# Fastino-DIOT.net
KiCad netlist of a schematic drawn in Altium Designer
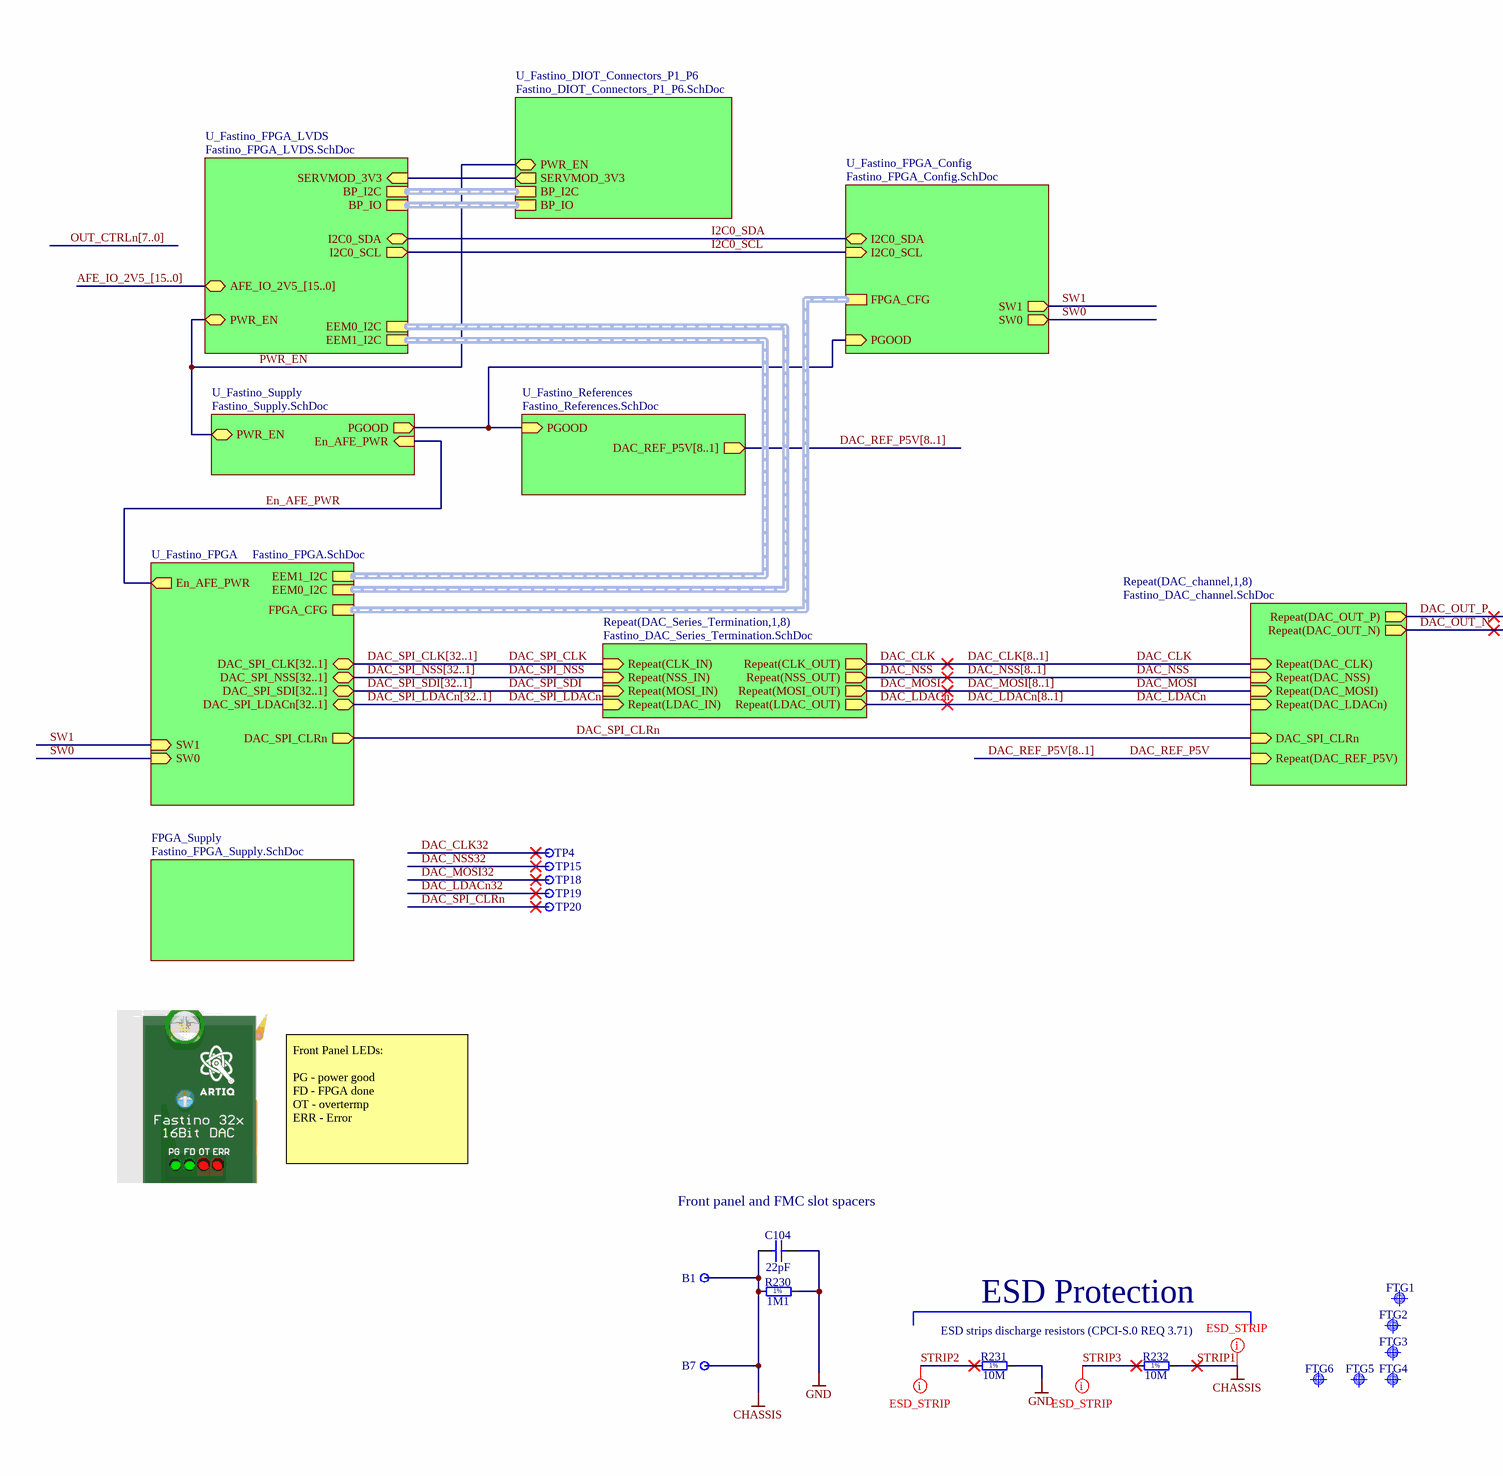
[diagram p0: Fastino-DIOT.schdoc, left]
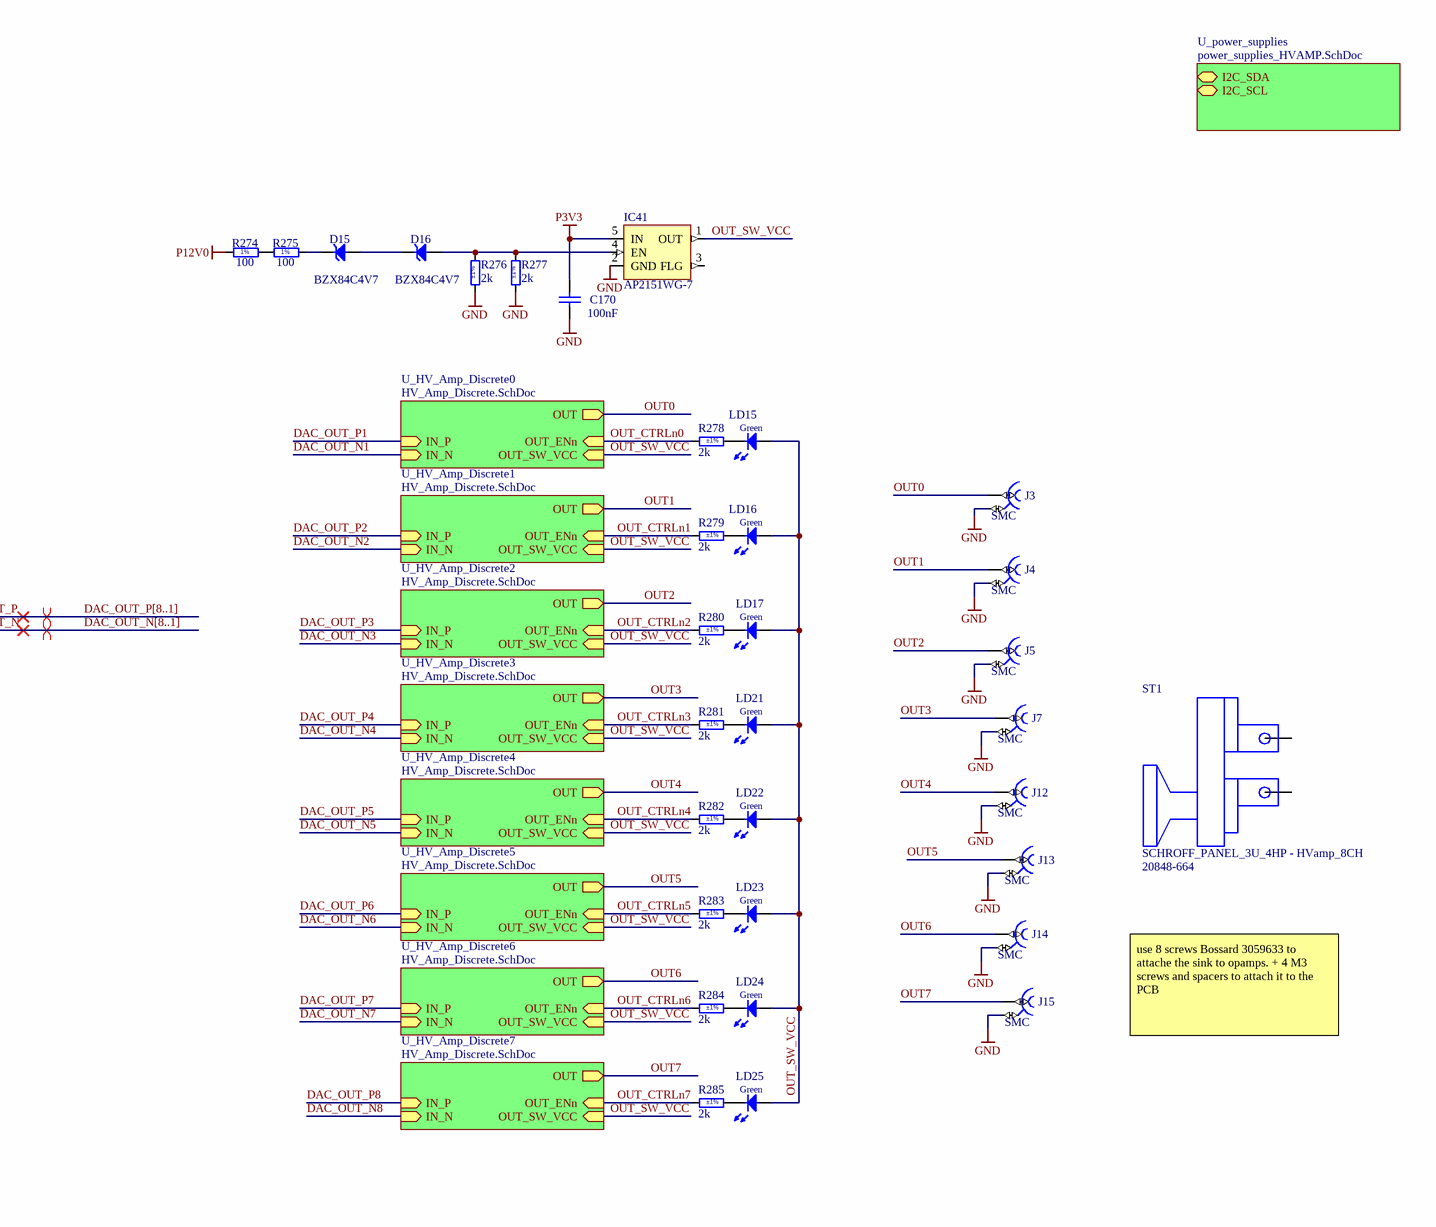
[diagram p1: Fastino-DIOT.schdoc, right]

(export (version "E")
  (design (tool "Eeschema 10.0.6"))
  (components
    (comp (ref "B1")
      (value "Plated Hole")
      (footprint "MTG270_500")
      (description "Single Terminal Socket")
      (fields (field (name "PART NUMBER") "PLATED_HOLE2.7_PAD5.0") (field (name "AUTHOR") "CERN DEM JMW"))
      (libsource (lib "Eletro-mechanical") (part "Single Terminal Socket"))
    )
    (comp (ref "B7")
      (value "Plated Hole")
      (footprint "MTG270_500")
      (description "Single Terminal Socket")
      (fields (field (name "PART NUMBER") "PLATED_HOLE2.7_PAD5.0") (field (name "AUTHOR") "CERN DEM JMW"))
      (libsource (lib "Eletro-mechanical") (part "Single Terminal Socket"))
    )
    (comp (ref "C104")
      (value "22pF")
      (footprint "CAPC1005X55N")
      (description "Non-polarised capacitor")
      (fields
        (field (name "PART NUMBER") "CC0402_22PF_50V_5%_C0G")
        (field (name "VOLTAGE") "50V")
        (field (name "AUTHOR") "CERN DEM JLC")
      )
      (libsource (lib "Capacitors") (part "Capacitor - non polarized"))
    )
    (comp (ref "C170")
      (value "100nF")
      (footprint "CAPC1005X55N")
      (description "Non-polarised capacitor")
      (fields
        (field (name "PART NUMBER") "CC0402_100NF_16V_10%_X5R")
        (field (name "VOLTAGE") "16V")
        (field (name "AUTHOR") "CERN DEM JLC")
      )
      (libsource (lib "Capacitors") (part "Capacitor - non polarized"))
    )
    (comp (ref "D15")
      (value "BZX84C4V7")
      (footprint "SOT95P240X130-3N")
      (description "Diode Zener Anode Pin 1 Cathode Pin 3 (Pas de pin 2)")
      (fields
        (field (name "VOLTAGE") "4V7")
        (field (name "POWER") "350mW")
        (field (name "AUTHOR") "CERN DEM JLC")
      )
      (libsource (lib "ICs And Semiconductors") (part "Diode Zener A1C3"))
    )
    (comp (ref "D16")
      (value "BZX84C4V7")
      (footprint "SOT95P240X130-3N")
      (description "Diode Zener Anode Pin 1 Cathode Pin 3 (Pas de pin 2)")
      (fields
        (field (name "VOLTAGE") "4V7")
        (field (name "POWER") "350mW")
        (field (name "AUTHOR") "CERN DEM JLC")
      )
      (libsource (lib "ICs And Semiconductors") (part "Diode Zener A1C3"))
    )
    (comp (ref "FTG1")
      (value "Use only in PCB")
      (footprint "FIDUCIAL_TOP_C100-200")
      (description "Fiducial Target")
      (fields (field (name "PART NUMBER") "FIDUCIAL_TARGET_C100-200") (field (name "AUTHOR") "CERN DEM JLC"))
      (libsource (lib "Eletro-mechanical") (part "Fiducial Target"))
    )
    (comp (ref "FTG2")
      (value "Use only in PCB")
      (footprint "FIDUCIAL_TOP_S100-200")
      (description "Fiducial Target")
      (fields (field (name "PART NUMBER") "FIDUCIAL_TARGET_S100-200") (field (name "AUTHOR") "CERN DEM JLC"))
      (libsource (lib "Eletro-mechanical") (part "Fiducial Target"))
    )
    (comp (ref "FTG3")
      (value "Use only in PCB")
      (footprint "FIDUCIAL_TOP_S100-200")
      (description "Fiducial Target")
      (fields (field (name "PART NUMBER") "FIDUCIAL_TARGET_S100-200") (field (name "AUTHOR") "CERN DEM JLC"))
      (libsource (lib "Eletro-mechanical") (part "Fiducial Target"))
    )
    (comp (ref "FTG4")
      (value "Use only in PCB")
      (footprint "FIDUCIAL_TOP_S100-200")
      (description "Fiducial Target")
      (fields (field (name "PART NUMBER") "FIDUCIAL_TARGET_S100-200") (field (name "AUTHOR") "CERN DEM JLC"))
      (libsource (lib "Eletro-mechanical") (part "Fiducial Target"))
    )
    (comp (ref "FTG5")
      (value "Use only in PCB")
      (footprint "FIDUCIAL_TOP_S100-200")
      (description "Fiducial Target")
      (fields (field (name "PART NUMBER") "FIDUCIAL_TARGET_S100-200") (field (name "AUTHOR") "CERN DEM JLC"))
      (libsource (lib "Eletro-mechanical") (part "Fiducial Target"))
    )
    (comp (ref "FTG6")
      (value "Use only in PCB")
      (footprint "FIDUCIAL_TOP_S100-200")
      (description "Fiducial Target")
      (fields (field (name "PART NUMBER") "FIDUCIAL_TARGET_S100-200") (field (name "AUTHOR") "CERN DEM JLC"))
      (libsource (lib "Eletro-mechanical") (part "Fiducial Target"))
    )
    (comp (ref "IC41")
      (value "AP2151WG-7")
      (footprint "SOT23-5")
      (description "0.5A SINGLE CHANNEL CURRENT- LIMITED POWER Switch")
      (libsource (lib "ICs_Analog_Interfaces") (part "IFC_AP2151"))
    )
    (comp (ref "J3")
      (value "SMC")
      (footprint "JOHNSON_131-6701-341")
      (fields
        (field (name "PART NUMBER") "JOHNSON_131-6701-341")
        (field (name "MANUFACTURER") "JOHNSON")
        (field (name "MANUFACTURER PART NUMBER") "131-6701-341")
        (field (name "AUTHOR") "CERN DEM JLC")
      )
      (libsource (lib "Connectors") (part "Coax_1Female_1Shield"))
    )
    (comp (ref "J4")
      (value "SMC")
      (footprint "JOHNSON_131-6701-341")
      (fields
        (field (name "PART NUMBER") "JOHNSON_131-6701-341")
        (field (name "MANUFACTURER") "JOHNSON")
        (field (name "MANUFACTURER PART NUMBER") "131-6701-341")
        (field (name "AUTHOR") "CERN DEM JLC")
      )
      (libsource (lib "Connectors") (part "Coax_1Female_1Shield"))
    )
    (comp (ref "J5")
      (value "SMC")
      (footprint "JOHNSON_131-6701-341")
      (fields
        (field (name "PART NUMBER") "JOHNSON_131-6701-341")
        (field (name "MANUFACTURER") "JOHNSON")
        (field (name "MANUFACTURER PART NUMBER") "131-6701-341")
        (field (name "AUTHOR") "CERN DEM JLC")
      )
      (libsource (lib "Connectors") (part "Coax_1Female_1Shield"))
    )
    (comp (ref "J7")
      (value "SMC")
      (footprint "JOHNSON_131-6701-341")
      (fields
        (field (name "PART NUMBER") "JOHNSON_131-6701-341")
        (field (name "MANUFACTURER") "JOHNSON")
        (field (name "MANUFACTURER PART NUMBER") "131-6701-341")
        (field (name "AUTHOR") "CERN DEM JLC")
      )
      (libsource (lib "Connectors") (part "Coax_1Female_1Shield"))
    )
    (comp (ref "J12")
      (value "SMC")
      (footprint "JOHNSON_131-6701-341")
      (fields
        (field (name "PART NUMBER") "JOHNSON_131-6701-341")
        (field (name "MANUFACTURER") "JOHNSON")
        (field (name "MANUFACTURER PART NUMBER") "131-6701-341")
        (field (name "AUTHOR") "CERN DEM JLC")
      )
      (libsource (lib "Connectors") (part "Coax_1Female_1Shield"))
    )
    (comp (ref "J13")
      (value "SMC")
      (footprint "JOHNSON_131-6701-341")
      (fields
        (field (name "PART NUMBER") "JOHNSON_131-6701-341")
        (field (name "MANUFACTURER") "JOHNSON")
        (field (name "MANUFACTURER PART NUMBER") "131-6701-341")
        (field (name "AUTHOR") "CERN DEM JLC")
      )
      (libsource (lib "Connectors") (part "Coax_1Female_1Shield"))
    )
    (comp (ref "J14")
      (value "SMC")
      (footprint "JOHNSON_131-6701-341")
      (fields
        (field (name "PART NUMBER") "JOHNSON_131-6701-341")
        (field (name "MANUFACTURER") "JOHNSON")
        (field (name "MANUFACTURER PART NUMBER") "131-6701-341")
        (field (name "AUTHOR") "CERN DEM JLC")
      )
      (libsource (lib "Connectors") (part "Coax_1Female_1Shield"))
    )
    (comp (ref "J15")
      (value "SMC")
      (footprint "JOHNSON_131-6701-341")
      (fields
        (field (name "PART NUMBER") "JOHNSON_131-6701-341")
        (field (name "MANUFACTURER") "JOHNSON")
        (field (name "MANUFACTURER PART NUMBER") "131-6701-341")
        (field (name "AUTHOR") "CERN DEM JLC")
      )
      (libsource (lib "Connectors") (part "Coax_1Female_1Shield"))
    )
    (comp (ref "LD15")
      (value "Green")
      (footprint "LED_AVAGO_HSME-C120")
      (description "LED Green 1C 2A")
      (fields
        (field (name "PART NUMBER") "LED_AVAGO_HSME-C120")
        (field (name "MANUFACTURER") "AVAGO TECHNOLOGIES")
        (field (name "AUTHOR") "CERN DEM JMW")
      )
      (libsource (lib "ICs And Semiconductors") (part "LED Green 1C 2A"))
    )
    (comp (ref "LD16")
      (value "Green")
      (footprint "LED_AVAGO_HSME-C120")
      (description "LED Green 1C 2A")
      (fields
        (field (name "PART NUMBER") "LED_AVAGO_HSME-C120")
        (field (name "MANUFACTURER") "AVAGO TECHNOLOGIES")
        (field (name "AUTHOR") "CERN DEM JMW")
      )
      (libsource (lib "ICs And Semiconductors") (part "LED Green 1C 2A"))
    )
    (comp (ref "LD17")
      (value "Green")
      (footprint "LED_AVAGO_HSME-C120")
      (description "LED Green 1C 2A")
      (fields
        (field (name "PART NUMBER") "LED_AVAGO_HSME-C120")
        (field (name "MANUFACTURER") "AVAGO TECHNOLOGIES")
        (field (name "AUTHOR") "CERN DEM JMW")
      )
      (libsource (lib "ICs And Semiconductors") (part "LED Green 1C 2A"))
    )
    (comp (ref "LD21")
      (value "Green")
      (footprint "LED_AVAGO_HSME-C120")
      (description "LED Green 1C 2A")
      (fields
        (field (name "PART NUMBER") "LED_AVAGO_HSME-C120")
        (field (name "MANUFACTURER") "AVAGO TECHNOLOGIES")
        (field (name "AUTHOR") "CERN DEM JMW")
      )
      (libsource (lib "ICs And Semiconductors") (part "LED Green 1C 2A"))
    )
    (comp (ref "LD22")
      (value "Green")
      (footprint "LED_AVAGO_HSME-C120")
      (description "LED Green 1C 2A")
      (fields
        (field (name "PART NUMBER") "LED_AVAGO_HSME-C120")
        (field (name "MANUFACTURER") "AVAGO TECHNOLOGIES")
        (field (name "AUTHOR") "CERN DEM JMW")
      )
      (libsource (lib "ICs And Semiconductors") (part "LED Green 1C 2A"))
    )
    (comp (ref "LD23")
      (value "Green")
      (footprint "LED_AVAGO_HSME-C120")
      (description "LED Green 1C 2A")
      (fields
        (field (name "PART NUMBER") "LED_AVAGO_HSME-C120")
        (field (name "MANUFACTURER") "AVAGO TECHNOLOGIES")
        (field (name "AUTHOR") "CERN DEM JMW")
      )
      (libsource (lib "ICs And Semiconductors") (part "LED Green 1C 2A"))
    )
    (comp (ref "LD24")
      (value "Green")
      (footprint "LED_AVAGO_HSME-C120")
      (description "LED Green 1C 2A")
      (fields
        (field (name "PART NUMBER") "LED_AVAGO_HSME-C120")
        (field (name "MANUFACTURER") "AVAGO TECHNOLOGIES")
        (field (name "AUTHOR") "CERN DEM JMW")
      )
      (libsource (lib "ICs And Semiconductors") (part "LED Green 1C 2A"))
    )
    (comp (ref "LD25")
      (value "Green")
      (footprint "LED_AVAGO_HSME-C120")
      (description "LED Green 1C 2A")
      (fields
        (field (name "PART NUMBER") "LED_AVAGO_HSME-C120")
        (field (name "MANUFACTURER") "AVAGO TECHNOLOGIES")
        (field (name "AUTHOR") "CERN DEM JMW")
      )
      (libsource (lib "ICs And Semiconductors") (part "LED Green 1C 2A"))
    )
    (comp (ref "R230")
      (value "1M1")
      (footprint "RESC2012X60N")
      (description "Resistor - 1%")
      (fields
        (field (name "PART NUMBER") "R0805_1M1_1%_0.125W_100PPM")
        (field (name "POWER") "0.125W")
        (field (name "AUTHOR") "CERN DEM JLC")
      )
      (libsource (lib "") (part "Resistor - 1%_1"))
    )
    (comp (ref "R231")
      (value "10M")
      (footprint "RESC2113X55N")
      (description "Resistor - 1%")
      (fields
        (field (name "PART NUMBER") "R0805_10M_1%_0.125W_100PPM_VISHAY_CRCW e3")
        (field (name "POWER") "0.125W")
        (field (name "AUTHOR") "CERN DEM BC")
      )
      (libsource (lib "") (part "Resistor - 1%_1"))
    )
    (comp (ref "R232")
      (value "10M")
      (footprint "RESC2113X55N")
      (description "Resistor - 1%")
      (fields
        (field (name "PART NUMBER") "R0805_10M_1%_0.125W_100PPM_VISHAY_CRCW e3")
        (field (name "POWER") "0.125W")
        (field (name "AUTHOR") "CERN DEM BC")
      )
      (libsource (lib "") (part "Resistor - 1%_1"))
    )
    (comp (ref "R274")
      (value "100")
      (footprint "RESC1005X40N")
      (description "Resistor - 1%")
      (fields
        (field (name "PART NUMBER") "R0402_100R_1%_0.0625W_100PPM")
        (field (name "POWER") "0.0625W")
        (field (name "AUTHOR") "CERN DEM JLC")
      )
      (libsource (lib "Resistors") (part "Resistor - 1%"))
    )
    (comp (ref "R275")
      (value "100")
      (footprint "RESC1005X40N")
      (description "Resistor - 1%")
      (fields
        (field (name "PART NUMBER") "R0402_100R_1%_0.0625W_100PPM")
        (field (name "POWER") "0.0625W")
        (field (name "AUTHOR") "CERN DEM JLC")
      )
      (libsource (lib "Resistors") (part "Resistor - 1%"))
    )
    (comp (ref "R276")
      (value "2k")
      (footprint "RESC1005X40N")
      (description "Resistor - 1%")
      (fields
        (field (name "PART NUMBER") "R0402_2K_1%_0.0625W_100PPM")
        (field (name "POWER") "0.0625W")
        (field (name "TOLERANCE") "±1%")
        (field (name "AUTHOR") "CERN DEM JLC")
      )
      (libsource (lib "Resistors") (part "Resistor - 1%"))
    )
    (comp (ref "R277")
      (value "2k")
      (footprint "RESC1005X40N")
      (description "Resistor - 1%")
      (fields
        (field (name "PART NUMBER") "R0402_2K_1%_0.0625W_100PPM")
        (field (name "POWER") "0.0625W")
        (field (name "TOLERANCE") "±1%")
        (field (name "AUTHOR") "CERN DEM JLC")
      )
      (libsource (lib "Resistors") (part "Resistor - 1%"))
    )
    (comp (ref "R278")
      (value "2k")
      (footprint "RESC1005X40N")
      (description "Resistor - 1%")
      (fields
        (field (name "PART NUMBER") "R0402_2K_1%_0.0625W_100PPM")
        (field (name "POWER") "0.0625W")
        (field (name "TOLERANCE") "±1%")
        (field (name "AUTHOR") "CERN DEM JLC")
      )
      (libsource (lib "Resistors") (part "Resistor - 1%"))
    )
    (comp (ref "R279")
      (value "2k")
      (footprint "RESC1005X40N")
      (description "Resistor - 1%")
      (fields
        (field (name "PART NUMBER") "R0402_2K_1%_0.0625W_100PPM")
        (field (name "POWER") "0.0625W")
        (field (name "TOLERANCE") "±1%")
        (field (name "AUTHOR") "CERN DEM JLC")
      )
      (libsource (lib "Resistors") (part "Resistor - 1%"))
    )
    (comp (ref "R280")
      (value "2k")
      (footprint "RESC1005X40N")
      (description "Resistor - 1%")
      (fields
        (field (name "PART NUMBER") "R0402_2K_1%_0.0625W_100PPM")
        (field (name "POWER") "0.0625W")
        (field (name "TOLERANCE") "±1%")
        (field (name "AUTHOR") "CERN DEM JLC")
      )
      (libsource (lib "Resistors") (part "Resistor - 1%"))
    )
    (comp (ref "R281")
      (value "2k")
      (footprint "RESC1005X40N")
      (description "Resistor - 1%")
      (fields
        (field (name "PART NUMBER") "R0402_2K_1%_0.0625W_100PPM")
        (field (name "POWER") "0.0625W")
        (field (name "TOLERANCE") "±1%")
        (field (name "AUTHOR") "CERN DEM JLC")
      )
      (libsource (lib "Resistors") (part "Resistor - 1%"))
    )
    (comp (ref "R282")
      (value "2k")
      (footprint "RESC1005X40N")
      (description "Resistor - 1%")
      (fields
        (field (name "PART NUMBER") "R0402_2K_1%_0.0625W_100PPM")
        (field (name "POWER") "0.0625W")
        (field (name "TOLERANCE") "±1%")
        (field (name "AUTHOR") "CERN DEM JLC")
      )
      (libsource (lib "Resistors") (part "Resistor - 1%"))
    )
    (comp (ref "R283")
      (value "2k")
      (footprint "RESC1005X40N")
      (description "Resistor - 1%")
      (fields
        (field (name "PART NUMBER") "R0402_2K_1%_0.0625W_100PPM")
        (field (name "POWER") "0.0625W")
        (field (name "TOLERANCE") "±1%")
        (field (name "AUTHOR") "CERN DEM JLC")
      )
      (libsource (lib "Resistors") (part "Resistor - 1%"))
    )
    (comp (ref "R284")
      (value "2k")
      (footprint "RESC1005X40N")
      (description "Resistor - 1%")
      (fields
        (field (name "PART NUMBER") "R0402_2K_1%_0.0625W_100PPM")
        (field (name "POWER") "0.0625W")
        (field (name "TOLERANCE") "±1%")
        (field (name "AUTHOR") "CERN DEM JLC")
      )
      (libsource (lib "Resistors") (part "Resistor - 1%"))
    )
    (comp (ref "R285")
      (value "2k")
      (footprint "RESC1005X40N")
      (description "Resistor - 1%")
      (fields
        (field (name "PART NUMBER") "R0402_2K_1%_0.0625W_100PPM")
        (field (name "POWER") "0.0625W")
        (field (name "TOLERANCE") "±1%")
        (field (name "AUTHOR") "CERN DEM JLC")
      )
      (libsource (lib "Resistors") (part "Resistor - 1%"))
    )
    (comp (ref "ST1")
      (value "SCHROFF_PANEL_3U_4HP - HVamp_8CH")
      (footprint "SCHROFF_PANEL_3U_4HP - HVamp_8CH")
      (description "Schroff 3HP 4U EUROCARD Panel")
      (fields
        (field (name "MANUFACTURER") "Schroff")
        (field (name "MANUFACTURER PART NUMBER") "20818-017")
        (field (name "MANUFACTURER PART NUMBER 2") "20848-664")
      )
      (libsource (lib "Mechanical") (part "SCHROFF_PANEL_3U_4HP - HVamp_8CH"))
    )
    (comp (ref "TP4")
      (value "Test Point")
      (footprint "TPS127")
      (fields (field (name "PART NUMBER") "SMD_PAD_1.27X1.27MM") (field (name "AUTHOR") "CERN DEM JLC"))
      (libsource (lib "Eletro-mechanical") (part "Test Point"))
    )
    (comp (ref "TP15")
      (value "Test Point")
      (footprint "TPS127")
      (fields (field (name "PART NUMBER") "SMD_PAD_1.27X1.27MM") (field (name "AUTHOR") "CERN DEM JLC"))
      (libsource (lib "Eletro-mechanical") (part "Test Point"))
    )
    (comp (ref "TP18")
      (value "Test Point")
      (footprint "TPS127")
      (fields (field (name "PART NUMBER") "SMD_PAD_1.27X1.27MM") (field (name "AUTHOR") "CERN DEM JLC"))
      (libsource (lib "Eletro-mechanical") (part "Test Point"))
    )
    (comp (ref "TP19")
      (value "Test Point")
      (footprint "TPS127")
      (fields (field (name "PART NUMBER") "SMD_PAD_1.27X1.27MM") (field (name "AUTHOR") "CERN DEM JLC"))
      (libsource (lib "Eletro-mechanical") (part "Test Point"))
    )
    (comp (ref "TP20")
      (value "Test Point")
      (footprint "TPS127")
      (fields (field (name "PART NUMBER") "SMD_PAD_1.27X1.27MM") (field (name "AUTHOR") "CERN DEM JLC"))
      (libsource (lib "Eletro-mechanical") (part "Test Point"))
    )
  )
  (nets
    (net (code "189") (name "/DAC_CLK32") (class "Default")
      (node (ref "TP4") (pin "1") (pinfunction "1_1") (pintype "bidirectional"))
    )
    (net (code "192") (name "/DAC_LDACn32") (class "Default")
      (node (ref "TP19") (pin "1") (pinfunction "1_1") (pintype "bidirectional"))
    )
    (net (code "195") (name "/DAC_MOSI32") (class "Default")
      (node (ref "TP18") (pin "1") (pinfunction "1_1") (pintype "bidirectional"))
    )
    (net (code "198") (name "/DAC_NSS32") (class "Default")
      (node (ref "TP15") (pin "1") (pinfunction "1_1") (pintype "bidirectional"))
    )
    (net (code "224") (name "/DAC_SPI_CLRn") (class "Default")
      (node (ref "TP20") (pin "1") (pinfunction "1_1") (pintype "bidirectional"))
    )
    (net (code "239") (name "/OUT0") (class "Default")
      (node (ref "J3") (pin "1") (pinfunction "1_1") (pintype "bidirectional"))
    )
    (net (code "240") (name "/OUT1") (class "Default")
      (node (ref "J4") (pin "1") (pinfunction "1_1") (pintype "bidirectional"))
    )
    (net (code "241") (name "/OUT2") (class "Default")
      (node (ref "J5") (pin "1") (pinfunction "1_1") (pintype "bidirectional"))
    )
    (net (code "242") (name "/OUT3") (class "Default")
      (node (ref "J7") (pin "1") (pinfunction "1_1") (pintype "bidirectional"))
    )
    (net (code "243") (name "/OUT4") (class "Default")
      (node (ref "J12") (pin "1") (pinfunction "1_1") (pintype "bidirectional"))
    )
    (net (code "244") (name "/OUT5") (class "Default")
      (node (ref "J13") (pin "1") (pinfunction "1_1") (pintype "bidirectional"))
    )
    (net (code "245") (name "/OUT6") (class "Default")
      (node (ref "J14") (pin "1") (pinfunction "1_1") (pintype "bidirectional"))
    )
    (net (code "246") (name "/OUT7") (class "Default")
      (node (ref "J15") (pin "1") (pinfunction "1_1") (pintype "bidirectional"))
    )
    (net (code "247") (name "/OUT_CTRLn0") (class "Default")
      (node (ref "R278") (pin "2") (pinfunction "2_2") (pintype "passive"))
    )
    (net (code "248") (name "/OUT_CTRLn1") (class "Default")
      (node (ref "R279") (pin "2") (pinfunction "2_2") (pintype "passive"))
    )
    (net (code "249") (name "/OUT_CTRLn2") (class "Default")
      (node (ref "R280") (pin "2") (pinfunction "2_2") (pintype "passive"))
    )
    (net (code "250") (name "/OUT_CTRLn3") (class "Default")
      (node (ref "R281") (pin "2") (pinfunction "2_2") (pintype "passive"))
    )
    (net (code "251") (name "/OUT_CTRLn4") (class "Default")
      (node (ref "R282") (pin "2") (pinfunction "2_2") (pintype "passive"))
    )
    (net (code "252") (name "/OUT_CTRLn5") (class "Default")
      (node (ref "R283") (pin "2") (pinfunction "2_2") (pintype "passive"))
    )
    (net (code "253") (name "/OUT_CTRLn6") (class "Default")
      (node (ref "R284") (pin "2") (pinfunction "2_2") (pintype "passive"))
    )
    (net (code "254") (name "/OUT_CTRLn7") (class "Default")
      (node (ref "R285") (pin "2") (pinfunction "2_2") (pintype "passive"))
    )
    (net (code "256") (name "/OUT_SW_VCC") (class "Default")
      (node (ref "IC41") (pin "1") (pinfunction "OUT_1") (pintype "output"))
      (node (ref "LD15") (pin "2") (pinfunction "A_2") (pintype "passive"))
      (node (ref "LD16") (pin "2") (pinfunction "A_2") (pintype "passive"))
      (node (ref "LD17") (pin "2") (pinfunction "A_2") (pintype "passive"))
      (node (ref "LD21") (pin "2") (pinfunction "A_2") (pintype "passive"))
      (node (ref "LD22") (pin "2") (pinfunction "A_2") (pintype "passive"))
      (node (ref "LD23") (pin "2") (pinfunction "A_2") (pintype "passive"))
      (node (ref "LD24") (pin "2") (pinfunction "A_2") (pintype "passive"))
      (node (ref "LD25") (pin "2") (pinfunction "A_2") (pintype "passive"))
    )
    (net (code "261") (name "/STRIP2") (class "Default")
      (node (ref "R231") (pin "1") (pinfunction "1_1") (pintype "passive+no_connect"))
    )
    (net (code "262") (name "/STRIP3") (class "Default")
      (node (ref "R232") (pin "1") (pinfunction "1_1") (pintype "passive+no_connect"))
    )
    (net (code "265") (name "CHASSIS") (class "Default")
      (node (ref "B1") (pin "1") (pinfunction "1_1") (pintype "bidirectional"))
      (node (ref "B7") (pin "1") (pinfunction "1_1") (pintype "bidirectional"))
      (node (ref "C104") (pin "1") (pinfunction "1_1") (pintype "passive"))
      (node (ref "R230") (pin "1") (pinfunction "1_1") (pintype "passive"))
      (node (ref "R232") (pin "2") (pinfunction "2_2") (pintype "passive"))
    )
    (net (code "266") (name "GND") (class "Default")
      (node (ref "C104") (pin "2") (pinfunction "2_2") (pintype "passive"))
      (node (ref "C170") (pin "1") (pinfunction "1_1") (pintype "passive"))
      (node (ref "IC41") (pin "2") (pinfunction "GND_2") (pintype "power_in"))
      (node (ref "J12") (pin "2") (pinfunction "2_2") (pintype "bidirectional"))
      (node (ref "J13") (pin "2") (pinfunction "2_2") (pintype "bidirectional"))
      (node (ref "J14") (pin "2") (pinfunction "2_2") (pintype "bidirectional"))
      (node (ref "J15") (pin "2") (pinfunction "2_2") (pintype "bidirectional"))
      (node (ref "J3") (pin "2") (pinfunction "2_2") (pintype "bidirectional"))
      (node (ref "J4") (pin "2") (pinfunction "2_2") (pintype "bidirectional"))
      (node (ref "J5") (pin "2") (pinfunction "2_2") (pintype "bidirectional"))
      (node (ref "J7") (pin "2") (pinfunction "2_2") (pintype "bidirectional"))
      (node (ref "R230") (pin "2") (pinfunction "2_2") (pintype "passive"))
      (node (ref "R231") (pin "2") (pinfunction "2_2") (pintype "passive"))
      (node (ref "R276") (pin "2") (pinfunction "2_2") (pintype "passive"))
      (node (ref "R277") (pin "2") (pinfunction "2_2") (pintype "passive"))
    )
    (net (code "267") (name "Net-(D15-A)") (class "Default")
      (node (ref "D15") (pin "1") (pinfunction "A_1") (pintype "passive"))
      (node (ref "D16") (pin "3") (pinfunction "C_3") (pintype "passive"))
    )
    (net (code "268") (name "Net-(D15-C)") (class "Default")
      (node (ref "D15") (pin "3") (pinfunction "C_3") (pintype "passive"))
      (node (ref "R275") (pin "2") (pinfunction "2_2") (pintype "passive"))
    )
    (net (code "269") (name "Net-(D16-A)") (class "Default")
      (node (ref "D16") (pin "1") (pinfunction "A_1") (pintype "passive"))
      (node (ref "IC41") (pin "4") (pinfunction "EN_4") (pintype "input"))
      (node (ref "R276") (pin "1") (pinfunction "1_1") (pintype "passive"))
      (node (ref "R277") (pin "1") (pinfunction "1_1") (pintype "passive"))
    )
    (net (code "270") (name "Net-(LD15-C)") (class "Default")
      (node (ref "LD15") (pin "1") (pinfunction "C_1") (pintype "passive"))
      (node (ref "R278") (pin "1") (pinfunction "1_1") (pintype "passive"))
    )
    (net (code "271") (name "Net-(LD16-C)") (class "Default")
      (node (ref "LD16") (pin "1") (pinfunction "C_1") (pintype "passive"))
      (node (ref "R279") (pin "1") (pinfunction "1_1") (pintype "passive"))
    )
    (net (code "272") (name "Net-(LD17-C)") (class "Default")
      (node (ref "LD17") (pin "1") (pinfunction "C_1") (pintype "passive"))
      (node (ref "R280") (pin "1") (pinfunction "1_1") (pintype "passive"))
    )
    (net (code "273") (name "Net-(LD21-C)") (class "Default")
      (node (ref "LD21") (pin "1") (pinfunction "C_1") (pintype "passive"))
      (node (ref "R281") (pin "1") (pinfunction "1_1") (pintype "passive"))
    )
    (net (code "274") (name "Net-(LD22-C)") (class "Default")
      (node (ref "LD22") (pin "1") (pinfunction "C_1") (pintype "passive"))
      (node (ref "R282") (pin "1") (pinfunction "1_1") (pintype "passive"))
    )
    (net (code "275") (name "Net-(LD23-C)") (class "Default")
      (node (ref "LD23") (pin "1") (pinfunction "C_1") (pintype "passive"))
      (node (ref "R283") (pin "1") (pinfunction "1_1") (pintype "passive"))
    )
    (net (code "276") (name "Net-(LD24-C)") (class "Default")
      (node (ref "LD24") (pin "1") (pinfunction "C_1") (pintype "passive"))
      (node (ref "R284") (pin "1") (pinfunction "1_1") (pintype "passive"))
    )
    (net (code "277") (name "Net-(LD25-C)") (class "Default")
      (node (ref "LD25") (pin "1") (pinfunction "C_1") (pintype "passive"))
      (node (ref "R285") (pin "1") (pinfunction "1_1") (pintype "passive"))
    )
    (net (code "278") (name "Net-(R274-Pad2)") (class "Default")
      (node (ref "R274") (pin "2") (pinfunction "2_2") (pintype "passive"))
      (node (ref "R275") (pin "1") (pinfunction "1_1") (pintype "passive"))
    )
    (net (code "279") (name "P3V3") (class "Default")
      (node (ref "C170") (pin "2") (pinfunction "2_2") (pintype "passive"))
      (node (ref "IC41") (pin "5") (pinfunction "IN_5") (pintype "power_in"))
    )
    (net (code "280") (name "P12V0") (class "Default")
      (node (ref "R274") (pin "1") (pinfunction "1_1") (pintype "passive"))
    )
    (net (code "281") (name "unconnected-(IC41-FLG-Pad3)") (class "Default")
      (node (ref "IC41") (pin "3") (pinfunction "FLG_3") (pintype "output"))
    )
    (net (code "282") (name "unconnected-(ST1-Pad0)") (class "Default")
      (node (ref "ST1") (pin "0") (pinfunction "0_0") (pintype "passive"))
    )
    (net (code "283") (name "unconnected-(ST1-Pad1)") (class "Default")
      (node (ref "ST1") (pin "1") (pinfunction "1_1") (pintype "passive"))
    )
  )
)
